# motoko_ice_dragon.net
KiCad netlist of a schematic drawn in EAGLE
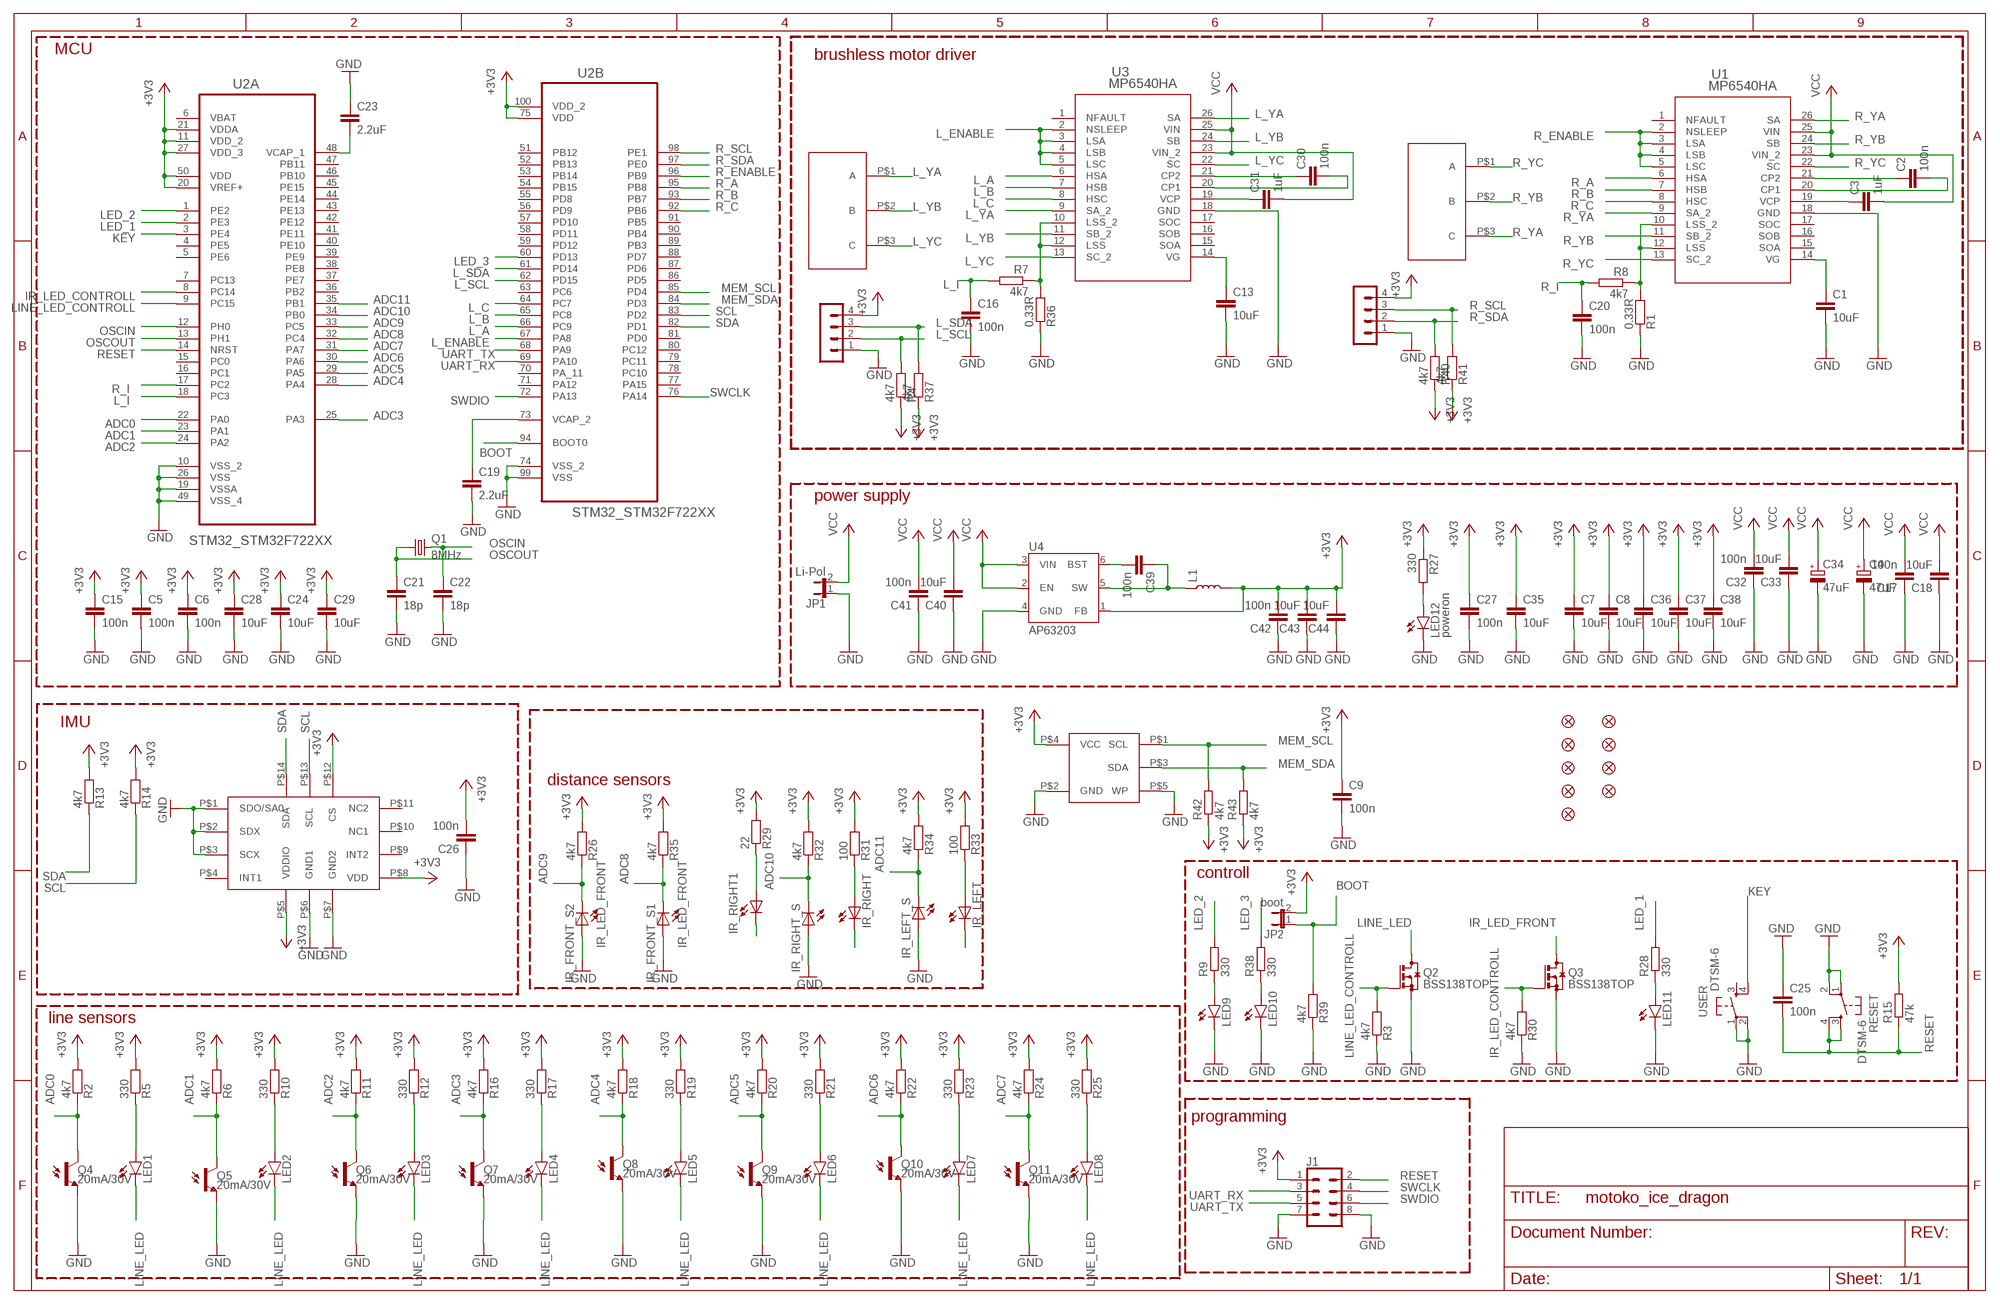
[diagram p0: schematic, sheet 1]

(export (version "E")
  (design (tool "Eeschema 10.0.6"))
  (components
    (comp (ref "C1")
      (value "10uF")
      (footprint "eagle-import:C0805")
      (libsource (lib "eagle-import") (part "C-EUC0805"))
    )
    (comp (ref "C2")
      (value "100n")
      (footprint "eagle-import:C0805")
      (libsource (lib "eagle-import") (part "C-EUC0805"))
    )
    (comp (ref "C3")
      (value "1uF")
      (footprint "eagle-import:C0805")
      (libsource (lib "eagle-import") (part "C-EUC0805"))
    )
    (comp (ref "C4")
      (value "47uF")
      (footprint "eagle-import:140CLH-1010")
      (libsource (lib "eagle-import") (part "CPOL-EU140CLH-1010"))
    )
    (comp (ref "C5")
      (value "100n")
      (footprint "eagle-import:C0805")
      (libsource (lib "eagle-import") (part "C-EUC0805"))
    )
    (comp (ref "C6")
      (value "100n")
      (footprint "eagle-import:C0805")
      (libsource (lib "eagle-import") (part "C-EUC0805"))
    )
    (comp (ref "C7")
      (value "10uF")
      (footprint "eagle-import:C0805")
      (libsource (lib "eagle-import") (part "C-EUC0805"))
    )
    (comp (ref "C8")
      (value "10uF")
      (footprint "eagle-import:C0805")
      (libsource (lib "eagle-import") (part "C-EUC0805"))
    )
    (comp (ref "C9")
      (value "100n")
      (footprint "eagle-import:C0805")
      (libsource (lib "eagle-import") (part "C-EUC0805"))
    )
    (comp (ref "C13")
      (value "10uF")
      (footprint "eagle-import:C0805")
      (libsource (lib "eagle-import") (part "C-EUC0805"))
    )
    (comp (ref "C15")
      (value "100n")
      (footprint "eagle-import:C0805")
      (libsource (lib "eagle-import") (part "C-EUC0805"))
    )
    (comp (ref "C16")
      (value "100n")
      (footprint "eagle-import:C0805")
      (libsource (lib "eagle-import") (part "C-EUC0805"))
    )
    (comp (ref "C17")
      (value "100n")
      (footprint "eagle-import:C0805")
      (libsource (lib "eagle-import") (part "C-EUC0805"))
    )
    (comp (ref "C18")
      (value "10uF")
      (footprint "eagle-import:C0805")
      (libsource (lib "eagle-import") (part "C-EUC0805"))
    )
    (comp (ref "C19")
      (value "2.2uF")
      (footprint "eagle-import:C0805")
      (libsource (lib "eagle-import") (part "C-EUC0805"))
    )
    (comp (ref "C20")
      (value "100n")
      (footprint "eagle-import:C0805")
      (libsource (lib "eagle-import") (part "C-EUC0805"))
    )
    (comp (ref "C21")
      (value "18p")
      (footprint "eagle-import:C0805")
      (libsource (lib "eagle-import") (part "C-EUC0805"))
    )
    (comp (ref "C22")
      (value "18p")
      (footprint "eagle-import:C0805")
      (libsource (lib "eagle-import") (part "C-EUC0805"))
    )
    (comp (ref "C23")
      (value "2.2uF")
      (footprint "eagle-import:C0805")
      (libsource (lib "eagle-import") (part "C-EUC0805"))
    )
    (comp (ref "C24")
      (value "10uF")
      (footprint "eagle-import:C0805")
      (libsource (lib "eagle-import") (part "C-EUC0805"))
    )
    (comp (ref "C25")
      (value "100n")
      (footprint "eagle-import:C0805")
      (libsource (lib "eagle-import") (part "C-EUC0805"))
    )
    (comp (ref "C26")
      (value "100n")
      (footprint "eagle-import:C0805")
      (libsource (lib "eagle-import") (part "C-EUC0805"))
    )
    (comp (ref "C27")
      (value "100n")
      (footprint "eagle-import:C0805")
      (libsource (lib "eagle-import") (part "C-EUC0805"))
    )
    (comp (ref "C28")
      (value "10uF")
      (footprint "eagle-import:C0805")
      (libsource (lib "eagle-import") (part "C-EUC0805"))
    )
    (comp (ref "C29")
      (value "10uF")
      (footprint "eagle-import:C0805")
      (libsource (lib "eagle-import") (part "C-EUC0805"))
    )
    (comp (ref "C30")
      (value "100n")
      (footprint "eagle-import:C0805")
      (libsource (lib "eagle-import") (part "C-EUC0805"))
    )
    (comp (ref "C31")
      (value "1uF")
      (footprint "eagle-import:C0805")
      (libsource (lib "eagle-import") (part "C-EUC0805"))
    )
    (comp (ref "C32")
      (value "100n")
      (footprint "eagle-import:C0805")
      (libsource (lib "eagle-import") (part "C-EUC0805"))
    )
    (comp (ref "C33")
      (value "10uF")
      (footprint "eagle-import:C0805")
      (libsource (lib "eagle-import") (part "C-EUC0805"))
    )
    (comp (ref "C34")
      (value "47uF")
      (footprint "eagle-import:140CLH-1010")
      (libsource (lib "eagle-import") (part "CPOL-EU140CLH-1010"))
    )
    (comp (ref "C35")
      (value "10uF")
      (footprint "eagle-import:C0805")
      (libsource (lib "eagle-import") (part "C-EUC0805"))
    )
    (comp (ref "C36")
      (value "10uF")
      (footprint "eagle-import:C0805")
      (libsource (lib "eagle-import") (part "C-EUC0805"))
    )
    (comp (ref "C37")
      (value "10uF")
      (footprint "eagle-import:C0805")
      (libsource (lib "eagle-import") (part "C-EUC0805"))
    )
    (comp (ref "C38")
      (value "10uF")
      (footprint "eagle-import:C0805")
      (libsource (lib "eagle-import") (part "C-EUC0805"))
    )
    (comp (ref "C39")
      (value "100n")
      (footprint "eagle-import:C0805")
      (libsource (lib "eagle-import") (part "C-EUC0805"))
    )
    (comp (ref "C40")
      (value "10uF")
      (footprint "eagle-import:C0805")
      (libsource (lib "eagle-import") (part "C-EUC0805"))
    )
    (comp (ref "C41")
      (value "100n")
      (footprint "eagle-import:C0805")
      (libsource (lib "eagle-import") (part "C-EUC0805"))
    )
    (comp (ref "C42")
      (value "100n")
      (footprint "eagle-import:C0805")
      (libsource (lib "eagle-import") (part "C-EUC0805"))
    )
    (comp (ref "C43")
      (value "10uF")
      (footprint "eagle-import:C0805")
      (libsource (lib "eagle-import") (part "C-EUC0805"))
    )
    (comp (ref "C44")
      (value "10uF")
      (footprint "eagle-import:C0805")
      (libsource (lib "eagle-import") (part "C-EUC0805"))
    )
    (comp (ref "FD1")
      (value "FIDUCIAL1X2")
      (footprint "eagle-import:FIDUCIAL-1X2")
      (libsource (lib "eagle-import") (part "FIDUCIAL1X2"))
    )
    (comp (ref "FD2")
      (value "FIDUCIAL1X2")
      (footprint "eagle-import:FIDUCIAL-1X2")
      (libsource (lib "eagle-import") (part "FIDUCIAL1X2"))
    )
    (comp (ref "FD3")
      (value "FIDUCIAL1X2")
      (footprint "eagle-import:FIDUCIAL-1X2")
      (libsource (lib "eagle-import") (part "FIDUCIAL1X2"))
    )
    (comp (ref "FD4")
      (value "FIDUCIAL1X2")
      (footprint "eagle-import:FIDUCIAL-1X2")
      (libsource (lib "eagle-import") (part "FIDUCIAL1X2"))
    )
    (comp (ref "FD5")
      (value "FIDUCIAL1X2")
      (footprint "eagle-import:FIDUCIAL-1X2")
      (libsource (lib "eagle-import") (part "FIDUCIAL1X2"))
    )
    (comp (ref "FD6")
      (value "FIDUCIAL1X2")
      (footprint "eagle-import:FIDUCIAL-1X2")
      (libsource (lib "eagle-import") (part "FIDUCIAL1X2"))
    )
    (comp (ref "FD7")
      (value "FIDUCIAL1X2")
      (footprint "eagle-import:FIDUCIAL-1X2")
      (libsource (lib "eagle-import") (part "FIDUCIAL1X2"))
    )
    (comp (ref "FD8")
      (value "FIDUCIAL1X2")
      (footprint "eagle-import:FIDUCIAL-1X2")
      (libsource (lib "eagle-import") (part "FIDUCIAL1X2"))
    )
    (comp (ref "FD9")
      (value "FIDUCIAL1X2")
      (footprint "eagle-import:FIDUCIAL-1X2")
      (libsource (lib "eagle-import") (part "FIDUCIAL1X2"))
    )
    (comp (ref "IR_FRONT_S1")
      (value "LED5MM")
      (footprint "eagle-import:LED5MM")
      (libsource (lib "eagle-import") (part "my_parts_LED5MM"))
    )
    (comp (ref "IR_FRONT_S2")
      (value "LED5MM")
      (footprint "eagle-import:LED5MM")
      (libsource (lib "eagle-import") (part "my_parts_LED5MM"))
    )
    (comp (ref "IR_LEFT")
      (value "LED5MM")
      (footprint "eagle-import:LED5MM")
      (libsource (lib "eagle-import") (part "my_parts_LED5MM"))
    )
    (comp (ref "IR_LEFT_S")
      (value "LED5MM")
      (footprint "eagle-import:LED5MM")
      (libsource (lib "eagle-import") (part "my_parts_LED5MM"))
    )
    (comp (ref "IR_RIGHT")
      (value "LED5MM")
      (footprint "eagle-import:LED5MM")
      (libsource (lib "eagle-import") (part "my_parts_LED5MM"))
    )
    (comp (ref "IR_RIGHT1")
      (value "LED5MM")
      (footprint "eagle-import:LED5MM")
      (libsource (lib "eagle-import") (part "my_parts_LED5MM"))
    )
    (comp (ref "IR_RIGHT_S")
      (value "LED5MM")
      (footprint "eagle-import:LED5MM")
      (libsource (lib "eagle-import") (part "my_parts_LED5MM"))
    )
    (comp (ref "J1")
      (value "CONN_04X2")
      (footprint "eagle-import:2X4")
      (libsource (lib "eagle-import") (part "CONN_04X2"))
    )
    (comp (ref "JP1")
      (value "Li-Pol")
      (footprint "eagle-import:JP1")
      (libsource (lib "eagle-import") (part "JP1E"))
    )
    (comp (ref "JP2")
      (value "boot")
      (footprint "eagle-import:JP1")
      (libsource (lib "eagle-import") (part "JP1E"))
    )
    (comp (ref "L1")
      (value "4.7uH, TYS50204R7N-10")
      (footprint "eagle-import:CR54")
      (libsource (lib "eagle-import") (part "INDUCTOR-CR54-3.3UH"))
    )
    (comp (ref "LED1")
      (value "LEDCHIPLED_1206")
      (footprint "eagle-import:CHIPLED_1206")
      (libsource (lib "eagle-import") (part "LEDCHIPLED_1206"))
    )
    (comp (ref "LED2")
      (value "LEDCHIPLED_1206")
      (footprint "eagle-import:CHIPLED_1206")
      (libsource (lib "eagle-import") (part "LEDCHIPLED_1206"))
    )
    (comp (ref "LED3")
      (value "LEDCHIPLED_1206")
      (footprint "eagle-import:CHIPLED_1206")
      (libsource (lib "eagle-import") (part "LEDCHIPLED_1206"))
    )
    (comp (ref "LED4")
      (value "LEDCHIPLED_1206")
      (footprint "eagle-import:CHIPLED_1206")
      (libsource (lib "eagle-import") (part "LEDCHIPLED_1206"))
    )
    (comp (ref "LED5")
      (value "LEDCHIPLED_1206")
      (footprint "eagle-import:CHIPLED_1206")
      (libsource (lib "eagle-import") (part "LEDCHIPLED_1206"))
    )
    (comp (ref "LED6")
      (value "LEDCHIPLED_1206")
      (footprint "eagle-import:CHIPLED_1206")
      (libsource (lib "eagle-import") (part "LEDCHIPLED_1206"))
    )
    (comp (ref "LED7")
      (value "LEDCHIPLED_1206")
      (footprint "eagle-import:CHIPLED_1206")
      (libsource (lib "eagle-import") (part "LEDCHIPLED_1206"))
    )
    (comp (ref "LED8")
      (value "LEDCHIPLED_1206")
      (footprint "eagle-import:CHIPLED_1206")
      (libsource (lib "eagle-import") (part "LEDCHIPLED_1206"))
    )
    (comp (ref "LED9")
      (value "LEDCHIPLED_1206")
      (footprint "eagle-import:CHIPLED_1206")
      (libsource (lib "eagle-import") (part "LEDCHIPLED_1206"))
    )
    (comp (ref "LED10")
      (value "LEDCHIPLED_1206")
      (footprint "eagle-import:CHIPLED_1206")
      (libsource (lib "eagle-import") (part "LEDCHIPLED_1206"))
    )
    (comp (ref "LED11")
      (value "LEDCHIPLED_1206")
      (footprint "eagle-import:CHIPLED_1206")
      (libsource (lib "eagle-import") (part "LEDCHIPLED_1206"))
    )
    (comp (ref "LED12")
      (value "poweron")
      (footprint "eagle-import:CHIPLED_1206")
      (libsource (lib "eagle-import") (part "LEDCHIPLED_1206"))
    )
    (comp (ref "L_ENCODER")
      (value "MA04-1")
      (footprint "eagle-import:MA04-1")
      (libsource (lib "eagle-import") (part "MA04-1"))
    )
    (comp (ref "L_ENCODER1")
      (value "MA04-1")
      (footprint "eagle-import:MA04-1")
      (libsource (lib "eagle-import") (part "MA04-1"))
    )
    (comp (ref "Q1")
      (value "8MHz")
      (footprint "eagle-import:CTS406")
      (libsource (lib "eagle-import") (part "CRYSTALCTS406"))
    )
    (comp (ref "Q2")
      (value "BSS138TOP")
      (footprint "eagle-import:SOT23")
      (libsource (lib "eagle-import") (part "BSS138TOP"))
    )
    (comp (ref "Q3")
      (value "BSS138TOP")
      (footprint "eagle-import:SOT23")
      (libsource (lib "eagle-import") (part "BSS138TOP"))
    )
    (comp (ref "Q4")
      (value "20mA/30V")
      (footprint "eagle-import:PT17-21C-L41-TR8")
      (libsource (lib "eagle-import") (part "PHOTOTRANSISTORPT17-21C-L41-TR8"))
    )
    (comp (ref "Q5")
      (value "20mA/30V")
      (footprint "eagle-import:PT17-21C-L41-TR8")
      (libsource (lib "eagle-import") (part "PHOTOTRANSISTORPT17-21C-L41-TR8"))
    )
    (comp (ref "Q6")
      (value "20mA/30V")
      (footprint "eagle-import:PT17-21C-L41-TR8")
      (libsource (lib "eagle-import") (part "PHOTOTRANSISTORPT17-21C-L41-TR8"))
    )
    (comp (ref "Q7")
      (value "20mA/30V")
      (footprint "eagle-import:PT17-21C-L41-TR8")
      (libsource (lib "eagle-import") (part "PHOTOTRANSISTORPT17-21C-L41-TR8"))
    )
    (comp (ref "Q8")
      (value "20mA/30V")
      (footprint "eagle-import:PT17-21C-L41-TR8")
      (libsource (lib "eagle-import") (part "PHOTOTRANSISTORPT17-21C-L41-TR8"))
    )
    (comp (ref "Q9")
      (value "20mA/30V")
      (footprint "eagle-import:PT17-21C-L41-TR8")
      (libsource (lib "eagle-import") (part "PHOTOTRANSISTORPT17-21C-L41-TR8"))
    )
    (comp (ref "Q10")
      (value "20mA/30V")
      (footprint "eagle-import:PT17-21C-L41-TR8")
      (libsource (lib "eagle-import") (part "PHOTOTRANSISTORPT17-21C-L41-TR8"))
    )
    (comp (ref "Q11")
      (value "20mA/30V")
      (footprint "eagle-import:PT17-21C-L41-TR8")
      (libsource (lib "eagle-import") (part "PHOTOTRANSISTORPT17-21C-L41-TR8"))
    )
    (comp (ref "R1")
      (value "0.33R")
      (footprint "eagle-import:M1206")
      (libsource (lib "eagle-import") (part "R-EU_M1206"))
    )
    (comp (ref "R2")
      (value "4k7")
      (footprint "eagle-import:M0805")
      (libsource (lib "eagle-import") (part "resistor_348_R-EU_M0805"))
    )
    (comp (ref "R3")
      (value "4k7")
      (footprint "eagle-import:M0805")
      (libsource (lib "eagle-import") (part "resistor_348_R-EU_M0805"))
    )
    (comp (ref "R4")
      (value "4k7")
      (footprint "eagle-import:M0805")
      (libsource (lib "eagle-import") (part "resistor_348_R-EU_M0805"))
    )
    (comp (ref "R5")
      (value "330")
      (footprint "eagle-import:M0805")
      (libsource (lib "eagle-import") (part "resistor_348_R-EU_M0805"))
    )
    (comp (ref "R6")
      (value "4k7")
      (footprint "eagle-import:M0805")
      (libsource (lib "eagle-import") (part "resistor_348_R-EU_M0805"))
    )
    (comp (ref "R7")
      (value "4k7")
      (footprint "eagle-import:M0805")
      (libsource (lib "eagle-import") (part "resistor_348_R-EU_M0805"))
    )
    (comp (ref "R8")
      (value "4k7")
      (footprint "eagle-import:M0805")
      (libsource (lib "eagle-import") (part "resistor_348_R-EU_M0805"))
    )
    (comp (ref "R9")
      (value "330")
      (footprint "eagle-import:M0805")
      (libsource (lib "eagle-import") (part "resistor_348_R-EU_M0805"))
    )
    (comp (ref "R10")
      (value "330")
      (footprint "eagle-import:M0805")
      (libsource (lib "eagle-import") (part "resistor_348_R-EU_M0805"))
    )
    (comp (ref "R11")
      (value "4k7")
      (footprint "eagle-import:M0805")
      (libsource (lib "eagle-import") (part "resistor_348_R-EU_M0805"))
    )
    (comp (ref "R12")
      (value "330")
      (footprint "eagle-import:M0805")
      (libsource (lib "eagle-import") (part "resistor_348_R-EU_M0805"))
    )
    (comp (ref "R13")
      (value "4k7")
      (footprint "eagle-import:M0805")
      (libsource (lib "eagle-import") (part "resistor_348_R-EU_M0805"))
    )
    (comp (ref "R14")
      (value "4k7")
      (footprint "eagle-import:M0805")
      (libsource (lib "eagle-import") (part "resistor_348_R-EU_M0805"))
    )
    (comp (ref "R15")
      (value "47k")
      (footprint "eagle-import:M0805")
      (libsource (lib "eagle-import") (part "resistor_348_R-EU_M0805"))
    )
    (comp (ref "R16")
      (value "4k7")
      (footprint "eagle-import:M0805")
      (libsource (lib "eagle-import") (part "resistor_348_R-EU_M0805"))
    )
    (comp (ref "R17")
      (value "330")
      (footprint "eagle-import:M0805")
      (libsource (lib "eagle-import") (part "resistor_348_R-EU_M0805"))
    )
    (comp (ref "R18")
      (value "4k7")
      (footprint "eagle-import:M0805")
      (libsource (lib "eagle-import") (part "resistor_348_R-EU_M0805"))
    )
    (comp (ref "R19")
      (value "330")
      (footprint "eagle-import:M0805")
      (libsource (lib "eagle-import") (part "resistor_348_R-EU_M0805"))
    )
    (comp (ref "R20")
      (value "4k7")
      (footprint "eagle-import:M0805")
      (libsource (lib "eagle-import") (part "resistor_348_R-EU_M0805"))
    )
    (comp (ref "R21")
      (value "330")
      (footprint "eagle-import:M0805")
      (libsource (lib "eagle-import") (part "resistor_348_R-EU_M0805"))
    )
    (comp (ref "R22")
      (value "4k7")
      (footprint "eagle-import:M0805")
      (libsource (lib "eagle-import") (part "resistor_348_R-EU_M0805"))
    )
    (comp (ref "R23")
      (value "330")
      (footprint "eagle-import:M0805")
      (libsource (lib "eagle-import") (part "resistor_348_R-EU_M0805"))
    )
    (comp (ref "R24")
      (value "4k7")
      (footprint "eagle-import:M0805")
      (libsource (lib "eagle-import") (part "resistor_348_R-EU_M0805"))
    )
    (comp (ref "R25")
      (value "330")
      (footprint "eagle-import:M0805")
      (libsource (lib "eagle-import") (part "resistor_348_R-EU_M0805"))
    )
    (comp (ref "R26")
      (value "4k7")
      (footprint "eagle-import:M0805")
      (libsource (lib "eagle-import") (part "resistor_348_R-EU_M0805"))
    )
    (comp (ref "R27")
      (value "330")
      (footprint "eagle-import:M0805")
      (libsource (lib "eagle-import") (part "resistor_348_R-EU_M0805"))
    )
    (comp (ref "R28")
      (value "330")
      (footprint "eagle-import:M0805")
      (libsource (lib "eagle-import") (part "resistor_348_R-EU_M0805"))
    )
    (comp (ref "R29")
      (value "22")
      (footprint "eagle-import:M0805")
      (libsource (lib "eagle-import") (part "resistor_348_R-EU_M0805"))
    )
    (comp (ref "R30")
      (value "4k7")
      (footprint "eagle-import:M0805")
      (libsource (lib "eagle-import") (part "resistor_348_R-EU_M0805"))
    )
    (comp (ref "R31")
      (value "100")
      (footprint "eagle-import:M0805")
      (libsource (lib "eagle-import") (part "resistor_348_R-EU_M0805"))
    )
    (comp (ref "R32")
      (value "4k7")
      (footprint "eagle-import:M0805")
      (libsource (lib "eagle-import") (part "resistor_348_R-EU_M0805"))
    )
    (comp (ref "R33")
      (value "100")
      (footprint "eagle-import:M0805")
      (libsource (lib "eagle-import") (part "resistor_348_R-EU_M0805"))
    )
    (comp (ref "R34")
      (value "4k7")
      (footprint "eagle-import:M0805")
      (libsource (lib "eagle-import") (part "resistor_348_R-EU_M0805"))
    )
    (comp (ref "R35")
      (value "4k7")
      (footprint "eagle-import:M0805")
      (libsource (lib "eagle-import") (part "resistor_348_R-EU_M0805"))
    )
    (comp (ref "R36")
      (value "0.33R")
      (footprint "eagle-import:M1206")
      (libsource (lib "eagle-import") (part "R-EU_M1206"))
    )
    (comp (ref "R37")
      (value "4k7")
      (footprint "eagle-import:M0805")
      (libsource (lib "eagle-import") (part "resistor_348_R-EU_M0805"))
    )
    (comp (ref "R38")
      (value "330")
      (footprint "eagle-import:M0805")
      (libsource (lib "eagle-import") (part "resistor_348_R-EU_M0805"))
    )
    (comp (ref "R39")
      (value "4k7")
      (footprint "eagle-import:M0805")
      (libsource (lib "eagle-import") (part "resistor_348_R-EU_M0805"))
    )
    (comp (ref "R40")
      (value "4k7")
      (footprint "eagle-import:M0805")
      (libsource (lib "eagle-import") (part "resistor_348_R-EU_M0805"))
    )
    (comp (ref "R41")
      (value "4k7")
      (footprint "eagle-import:M0805")
      (libsource (lib "eagle-import") (part "resistor_348_R-EU_M0805"))
    )
    (comp (ref "R42")
      (value "4k7")
      (footprint "eagle-import:M0805")
      (libsource (lib "eagle-import") (part "R-EU_M0805"))
    )
    (comp (ref "R43")
      (value "4k7")
      (footprint "eagle-import:M0805")
      (libsource (lib "eagle-import") (part "R-EU_M0805"))
    )
    (comp (ref "RESET")
      (value "DTSM-6")
      (footprint "eagle-import:DTSM-6")
      (libsource (lib "eagle-import") (part "DTSM-6"))
    )
    (comp (ref "U$1")
      (value "BRUSHLESS_GIMBAL_MOTOR_WHEEL")
      (footprint "eagle-import:BRUSHLESS_GIMBAL_MOTOR_WHEEL")
      (libsource (lib "eagle-import") (part "BRUSHLESS_GIMBAL_MOTOR_WHEEL"))
    )
    (comp (ref "U$2")
      (value "BRUSHLESS_GIMBAL_MOTOR_WHEEL")
      (footprint "eagle-import:BRUSHLESS_GIMBAL_MOTOR_WHEEL")
      (libsource (lib "eagle-import") (part "BRUSHLESS_GIMBAL_MOTOR_WHEEL"))
    )
    (comp (ref "U$3")
      (value "LSM6DSM")
      (footprint "eagle-import:LGA14L")
      (libsource (lib "eagle-import") (part "LSM6DSM"))
    )
    (comp (ref "U$4")
      (value "24LC24_SOT23")
      (footprint "eagle-import:SOT23")
      (libsource (lib "eagle-import") (part "24LC24_SOT23"))
    )
    (comp (ref "U1")
      (value "MP6540HA")
      (footprint "eagle-import:QFN-5X5_MP6540HA_MNP")
      (fields (field (name "COPYRIGHT") "Copyright (C) 2018 Accelerated Designs. All rights reserved"))
      (libsource (lib "eagle-import") (part "MP6540HA"))
    )
    (comp (ref "U2")
      (value "STM32_STM32F722XX")
      (footprint "eagle-import:STM32_QFP50P1600X1600X160-100N")
      (fields (field (name "MPN") "STM32F407VET6"))
      (libsource (lib "eagle-import") (part "STM32_STM32F722XX"))
    )
    (comp (ref "U3")
      (value "MP6540HA")
      (footprint "eagle-import:QFN-5X5_MP6540HA_MNP")
      (fields (field (name "COPYRIGHT") "Copyright (C) 2018 Accelerated Designs. All rights reserved"))
      (libsource (lib "eagle-import") (part "MP6540HA"))
    )
    (comp (ref "U4")
      (value "AP63203")
      (footprint "eagle-import:SOT23-6")
      (libsource (lib "eagle-import") (part "AP63203"))
    )
    (comp (ref "USER")
      (value "DTSM-6")
      (footprint "eagle-import:DTSM-6")
      (libsource (lib "eagle-import") (part "DTSM-6"))
    )
  )
  (nets
    (net (code "1") (name "+3V3") (class "Default")
      (node (ref "C15") (pin "1") (pinfunction "1_1") (pintype "passive"))
      (node (ref "C24") (pin "1") (pinfunction "1_1") (pintype "passive"))
      (node (ref "C26") (pin "2") (pinfunction "2_2") (pintype "passive"))
      (node (ref "C27") (pin "1") (pinfunction "1_1") (pintype "passive"))
      (node (ref "C28") (pin "1") (pinfunction "1_1") (pintype "passive"))
      (node (ref "C29") (pin "1") (pinfunction "1_1") (pintype "passive"))
      (node (ref "C35") (pin "1") (pinfunction "1_1") (pintype "passive"))
      (node (ref "C36") (pin "1") (pinfunction "1_1") (pintype "passive"))
      (node (ref "C37") (pin "1") (pinfunction "1_1") (pintype "passive"))
      (node (ref "C38") (pin "1") (pinfunction "1_1") (pintype "passive"))
      (node (ref "C42") (pin "2") (pinfunction "2_2") (pintype "passive"))
      (node (ref "C43") (pin "2") (pinfunction "2_2") (pintype "passive"))
      (node (ref "C44") (pin "2") (pinfunction "2_2") (pintype "passive"))
      (node (ref "C5") (pin "1") (pinfunction "1_1") (pintype "passive"))
      (node (ref "C6") (pin "1") (pinfunction "1_1") (pintype "passive"))
      (node (ref "C7") (pin "1") (pinfunction "1_1") (pintype "passive"))
      (node (ref "C8") (pin "1") (pinfunction "1_1") (pintype "passive"))
      (node (ref "C9") (pin "1") (pinfunction "1_1") (pintype "passive"))
      (node (ref "J1") (pin "1") (pinfunction "1_1") (pintype "passive"))
      (node (ref "JP2") (pin "2") (pinfunction "2_2") (pintype "passive"))
      (node (ref "L1") (pin "P$2") (pinfunction "2_P$2") (pintype "passive"))
      (node (ref "L_ENCODER") (pin "4") (pinfunction "4_4") (pintype "passive"))
      (node (ref "L_ENCODER1") (pin "4") (pinfunction "4_4") (pintype "passive"))
      (node (ref "R10") (pin "2") (pinfunction "2_2") (pintype "passive"))
      (node (ref "R11") (pin "2") (pinfunction "2_2") (pintype "passive"))
      (node (ref "R12") (pin "2") (pinfunction "2_2") (pintype "passive"))
      (node (ref "R13") (pin "2") (pinfunction "2_2") (pintype "passive"))
      (node (ref "R14") (pin "2") (pinfunction "2_2") (pintype "passive"))
      (node (ref "R15") (pin "2") (pinfunction "2_2") (pintype "passive"))
      (node (ref "R16") (pin "2") (pinfunction "2_2") (pintype "passive"))
      (node (ref "R17") (pin "2") (pinfunction "2_2") (pintype "passive"))
      (node (ref "R18") (pin "2") (pinfunction "2_2") (pintype "passive"))
      (node (ref "R19") (pin "2") (pinfunction "2_2") (pintype "passive"))
      (node (ref "R2") (pin "2") (pinfunction "2_2") (pintype "passive"))
      (node (ref "R20") (pin "2") (pinfunction "2_2") (pintype "passive"))
      (node (ref "R21") (pin "2") (pinfunction "2_2") (pintype "passive"))
      (node (ref "R22") (pin "2") (pinfunction "2_2") (pintype "passive"))
      (node (ref "R23") (pin "2") (pinfunction "2_2") (pintype "passive"))
      (node (ref "R24") (pin "2") (pinfunction "2_2") (pintype "passive"))
      (node (ref "R25") (pin "2") (pinfunction "2_2") (pintype "passive"))
      (node (ref "R26") (pin "2") (pinfunction "2_2") (pintype "passive"))
      (node (ref "R27") (pin "1") (pinfunction "1_1") (pintype "passive"))
      (node (ref "R29") (pin "2") (pinfunction "2_2") (pintype "passive"))
      (node (ref "R31") (pin "2") (pinfunction "2_2") (pintype "passive"))
      (node (ref "R32") (pin "2") (pinfunction "2_2") (pintype "passive"))
      (node (ref "R33") (pin "2") (pinfunction "2_2") (pintype "passive"))
      (node (ref "R34") (pin "2") (pinfunction "2_2") (pintype "passive"))
      (node (ref "R35") (pin "2") (pinfunction "2_2") (pintype "passive"))
      (node (ref "R37") (pin "1") (pinfunction "1_1") (pintype "passive"))
      (node (ref "R4") (pin "1") (pinfunction "1_1") (pintype "passive"))
      (node (ref "R40") (pin "1") (pinfunction "1_1") (pintype "passive"))
      (node (ref "R41") (pin "1") (pinfunction "1_1") (pintype "passive"))
      (node (ref "R42") (pin "1") (pinfunction "1_1") (pintype "passive"))
      (node (ref "R43") (pin "1") (pinfunction "1_1") (pintype "passive"))
      (node (ref "R5") (pin "2") (pinfunction "2_2") (pintype "passive"))
      (node (ref "R6") (pin "2") (pinfunction "2_2") (pintype "passive"))
      (node (ref "U$3") (pin "P$12") (pinfunction "CS_P$12") (pintype "bidirectional"))
      (node (ref "U$3") (pin "P$5") (pinfunction "VDDIO_P$5") (pintype "bidirectional"))
      (node (ref "U$3") (pin "P$8") (pinfunction "VDD_P$8") (pintype "bidirectional"))
      (node (ref "U$4") (pin "P$4") (pinfunction "VCC_P$4") (pintype "bidirectional"))
      (node (ref "U2") (pin "100") (pinfunction "VDD_2_100") (pintype "power_in"))
      (node (ref "U2") (pin "11") (pinfunction "VDD_2_11") (pintype "power_in"))
      (node (ref "U2") (pin "20") (pinfunction "VREF+_20") (pintype "power_in"))
      (node (ref "U2") (pin "21") (pinfunction "VDDA_21") (pintype "power_in"))
      (node (ref "U2") (pin "27") (pinfunction "VDD_3_27") (pintype "power_in"))
      (node (ref "U2") (pin "50") (pinfunction "VDD_50") (pintype "power_in"))
      (node (ref "U2") (pin "75") (pinfunction "VDD_75") (pintype "power_in"))
      (node (ref "U4") (pin "1") (pinfunction "FB_1") (pintype "bidirectional"))
    )
    (net (code "2") (name "/ADC0") (class "Default")
      (node (ref "Q4") (pin "C") (pinfunction "C_C") (pintype "passive"))
      (node (ref "R2") (pin "1") (pinfunction "1_1") (pintype "passive"))
      (node (ref "U2") (pin "22") (pinfunction "PA0_22") (pintype "bidirectional"))
    )
    (net (code "3") (name "/ADC1") (class "Default")
      (node (ref "Q5") (pin "C") (pinfunction "C_C") (pintype "passive"))
      (node (ref "R6") (pin "1") (pinfunction "1_1") (pintype "passive"))
      (node (ref "U2") (pin "23") (pinfunction "PA1_23") (pintype "bidirectional"))
    )
    (net (code "4") (name "/ADC2") (class "Default")
      (node (ref "Q6") (pin "C") (pinfunction "C_C") (pintype "passive"))
      (node (ref "R11") (pin "1") (pinfunction "1_1") (pintype "passive"))
      (node (ref "U2") (pin "24") (pinfunction "PA2_24") (pintype "bidirectional"))
    )
    (net (code "5") (name "/ADC3") (class "Default")
      (node (ref "Q7") (pin "C") (pinfunction "C_C") (pintype "passive"))
      (node (ref "R16") (pin "1") (pinfunction "1_1") (pintype "passive"))
      (node (ref "U2") (pin "25") (pinfunction "PA3_25") (pintype "bidirectional"))
    )
    (net (code "6") (name "/ADC4") (class "Default")
      (node (ref "Q8") (pin "C") (pinfunction "C_C") (pintype "passive"))
      (node (ref "R18") (pin "1") (pinfunction "1_1") (pintype "passive"))
      (node (ref "U2") (pin "28") (pinfunction "PA4_28") (pintype "bidirectional"))
    )
    (net (code "7") (name "/ADC5") (class "Default")
      (node (ref "Q9") (pin "C") (pinfunction "C_C") (pintype "passive"))
      (node (ref "R20") (pin "1") (pinfunction "1_1") (pintype "passive"))
      (node (ref "U2") (pin "29") (pinfunction "PA5_29") (pintype "bidirectional"))
    )
    (net (code "8") (name "/ADC6") (class "Default")
      (node (ref "Q10") (pin "C") (pinfunction "C_C") (pintype "passive"))
      (node (ref "R22") (pin "1") (pinfunction "1_1") (pintype "passive"))
      (node (ref "U2") (pin "30") (pinfunction "PA6_30") (pintype "bidirectional"))
    )
    (net (code "9") (name "/ADC7") (class "Default")
      (node (ref "Q11") (pin "C") (pinfunction "C_C") (pintype "passive"))
      (node (ref "R24") (pin "1") (pinfunction "1_1") (pintype "passive"))
      (node (ref "U2") (pin "31") (pinfunction "PA7_31") (pintype "bidirectional"))
    )
    (net (code "10") (name "/ADC8") (class "Default")
      (node (ref "IR_FRONT_S1") (pin "K") (pinfunction "C_K") (pintype "passive"))
      (node (ref "R35") (pin "1") (pinfunction "1_1") (pintype "passive"))
      (node (ref "U2") (pin "32") (pinfunction "PC4_32") (pintype "bidirectional"))
    )
    (net (code "11") (name "/ADC9") (class "Default")
      (node (ref "IR_FRONT_S2") (pin "K") (pinfunction "C_K") (pintype "passive"))
      (node (ref "R26") (pin "1") (pinfunction "1_1") (pintype "passive"))
      (node (ref "U2") (pin "33") (pinfunction "PC5_33") (pintype "bidirectional"))
    )
    (net (code "12") (name "/ADC10") (class "Default")
      (node (ref "IR_RIGHT_S") (pin "K") (pinfunction "C_K") (pintype "passive"))
      (node (ref "R32") (pin "1") (pinfunction "1_1") (pintype "passive"))
      (node (ref "U2") (pin "34") (pinfunction "PB0_34") (pintype "bidirectional"))
    )
    (net (code "13") (name "/ADC11") (class "Default")
      (node (ref "IR_LEFT_S") (pin "K") (pinfunction "C_K") (pintype "passive"))
      (node (ref "R34") (pin "1") (pinfunction "1_1") (pintype "passive"))
      (node (ref "U2") (pin "35") (pinfunction "PB1_35") (pintype "bidirectional"))
    )
    (net (code "14") (name "/BOOT") (class "Default")
      (node (ref "JP2") (pin "1") (pinfunction "1_1") (pintype "passive"))
      (node (ref "R39") (pin "2") (pinfunction "2_2") (pintype "passive"))
      (node (ref "U2") (pin "94") (pinfunction "BOOT0_94") (pintype "input"))
    )
    (net (code "15") (name "/IR_LED_CONTROLL") (class "Default")
      (node (ref "Q3") (pin "1") (pinfunction "G_1") (pintype "passive"))
      (node (ref "R30") (pin "2") (pinfunction "2_2") (pintype "passive"))
      (node (ref "U2") (pin "8") (pinfunction "PC14_8") (pintype "bidirectional"))
    )
    (net (code "16") (name "/IR_LED_FRONT") (class "Default")
      (node (ref "IR_LEFT") (pin "K") (pinfunction "C_K") (pintype "passive"))
      (node (ref "IR_RIGHT") (pin "K") (pinfunction "C_K") (pintype "passive"))
      (node (ref "IR_RIGHT1") (pin "K") (pinfunction "C_K") (pintype "passive"))
      (node (ref "Q3") (pin "3") (pinfunction "D_3") (pintype "passive"))
    )
    (net (code "17") (name "/KEY") (class "Default")
      (node (ref "U2") (pin "3") (pinfunction "PE4_3") (pintype "bidirectional"))
      (node (ref "USER") (pin "4") (pinfunction "4_4") (pintype "passive"))
    )
    (net (code "18") (name "/LED_1") (class "Default")
      (node (ref "R28") (pin "2") (pinfunction "2_2") (pintype "passive"))
      (node (ref "U2") (pin "2") (pinfunction "PE3_2") (pintype "bidirectional"))
    )
    (net (code "19") (name "/LED_2") (class "Default")
      (node (ref "R9") (pin "2") (pinfunction "2_2") (pintype "passive"))
      (node (ref "U2") (pin "1") (pinfunction "PE2_1") (pintype "bidirectional"))
    )
    (net (code "20") (name "/LED_3") (class "Default")
      (node (ref "R38") (pin "2") (pinfunction "2_2") (pintype "passive"))
      (node (ref "U2") (pin "60") (pinfunction "PD13_60") (pintype "bidirectional"))
    )
    (net (code "21") (name "/LINE_LED") (class "Default")
      (node (ref "LED1") (pin "C") (pinfunction "C_C") (pintype "passive"))
      (node (ref "LED2") (pin "C") (pinfunction "C_C") (pintype "passive"))
      (node (ref "LED3") (pin "C") (pinfunction "C_C") (pintype "passive"))
      (node (ref "LED4") (pin "C") (pinfunction "C_C") (pintype "passive"))
      (node (ref "LED5") (pin "C") (pinfunction "C_C") (pintype "passive"))
      (node (ref "LED6") (pin "C") (pinfunction "C_C") (pintype "passive"))
      (node (ref "LED7") (pin "C") (pinfunction "C_C") (pintype "passive"))
      (node (ref "LED8") (pin "C") (pinfunction "C_C") (pintype "passive"))
      (node (ref "Q2") (pin "3") (pinfunction "D_3") (pintype "passive"))
    )
    (net (code "22") (name "/LINE_LED_CONTROLL") (class "Default")
      (node (ref "Q2") (pin "1") (pinfunction "G_1") (pintype "passive"))
      (node (ref "R3") (pin "2") (pinfunction "2_2") (pintype "passive"))
      (node (ref "U2") (pin "9") (pinfunction "PC15_9") (pintype "bidirectional"))
    )
    (net (code "23") (name "/L_A") (class "Default")
      (node (ref "U2") (pin "66") (pinfunction "PC9_66") (pintype "bidirectional"))
      (node (ref "U3") (pin "6") (pinfunction "HSA_6") (pintype "passive"))
    )
    (net (code "24") (name "/L_B") (class "Default")
      (node (ref "U2") (pin "65") (pinfunction "PC8_65") (pintype "bidirectional"))
      (node (ref "U3") (pin "7") (pinfunction "HSB_7") (pintype "passive"))
    )
    (net (code "25") (name "/L_C") (class "Default")
      (node (ref "U2") (pin "64") (pinfunction "PC7_64") (pintype "bidirectional"))
      (node (ref "U3") (pin "8") (pinfunction "HSC_8") (pintype "passive"))
    )
    (net (code "26") (name "/L_ENABLE") (class "Default")
      (node (ref "U2") (pin "67") (pinfunction "PA8_67") (pintype "bidirectional"))
      (node (ref "U3") (pin "2") (pinfunction "NSLEEP_2") (pintype "input"))
      (node (ref "U3") (pin "3") (pinfunction "LSA_3") (pintype "passive"))
      (node (ref "U3") (pin "4") (pinfunction "LSB_4") (pintype "passive"))
      (node (ref "U3") (pin "5") (pinfunction "LSC_5") (pintype "passive"))
    )
    (net (code "27") (name "/L_I") (class "Default")
      (node (ref "C16") (pin "1") (pinfunction "1_1") (pintype "passive"))
      (node (ref "R7") (pin "2") (pinfunction "2_2") (pintype "passive"))
      (node (ref "U2") (pin "18") (pinfunction "PC3_18") (pintype "bidirectional"))
    )
    (net (code "28") (name "/L_SCL") (class "Default")
      (node (ref "L_ENCODER") (pin "2") (pinfunction "2_2") (pintype "passive"))
      (node (ref "R4") (pin "2") (pinfunction "2_2") (pintype "passive"))
      (node (ref "U2") (pin "62") (pinfunction "PD15_62") (pintype "bidirectional"))
    )
    (net (code "29") (name "/L_SDA") (class "Default")
      (node (ref "L_ENCODER") (pin "3") (pinfunction "3_3") (pintype "passive"))
      (node (ref "R37") (pin "2") (pinfunction "2_2") (pintype "passive"))
      (node (ref "U2") (pin "61") (pinfunction "PD14_61") (pintype "bidirectional"))
    )
    (net (code "30") (name "/L_YA") (class "Default")
      (node (ref "U$1") (pin "P$1") (pinfunction "A_P$1") (pintype "input"))
      (node (ref "U3") (pin "26") (pinfunction "SA_26") (pintype "output"))
      (node (ref "U3") (pin "9") (pinfunction "SA_2_9") (pintype "output"))
    )
    (net (code "31") (name "/L_YB") (class "Default")
      (node (ref "U$1") (pin "P$2") (pinfunction "B_P$2") (pintype "input"))
      (node (ref "U3") (pin "11") (pinfunction "SB_2_11") (pintype "output"))
      (node (ref "U3") (pin "24") (pinfunction "SB_24") (pintype "output"))
    )
    (net (code "32") (name "/L_YC") (class "Default")
      (node (ref "U$1") (pin "P$3") (pinfunction "C_P$3") (pintype "input"))
      (node (ref "U3") (pin "13") (pinfunction "SC_2_13") (pintype "output"))
      (node (ref "U3") (pin "22") (pinfunction "SC_22") (pintype "output"))
    )
    (net (code "33") (name "/MEM_SCL") (class "Default")
      (node (ref "R42") (pin "2") (pinfunction "2_2") (pintype "passive"))
      (node (ref "U$4") (pin "P$1") (pinfunction "SCL_P$1") (pintype "bidirectional"))
      (node (ref "U2") (pin "85") (pinfunction "PD4_85") (pintype "bidirectional"))
    )
    (net (code "34") (name "/MEM_SDA") (class "Default")
      (node (ref "R43") (pin "2") (pinfunction "2_2") (pintype "passive"))
      (node (ref "U$4") (pin "P$3") (pinfunction "SDA_P$3") (pintype "bidirectional"))
      (node (ref "U2") (pin "84") (pinfunction "PD3_84") (pintype "bidirectional"))
    )
    (net (code "35") (name "/OSCIN") (class "Default")
      (node (ref "C22") (pin "1") (pinfunction "1_1") (pintype "passive"))
      (node (ref "Q1") (pin "3") (pinfunction "2_3") (pintype "passive"))
      (node (ref "U2") (pin "12") (pinfunction "PH0_12") (pintype "bidirectional"))
    )
    (net (code "36") (name "/OSCOUT") (class "Default")
      (node (ref "C21") (pin "1") (pinfunction "1_1") (pintype "passive"))
      (node (ref "Q1") (pin "1") (pinfunction "1_1") (pintype "passive"))
      (node (ref "U2") (pin "13") (pinfunction "PH1_13") (pintype "bidirectional"))
    )
    (net (code "37") (name "/RESET") (class "Default")
      (node (ref "C25") (pin "2") (pinfunction "2_2") (pintype "passive"))
      (node (ref "J1") (pin "2") (pinfunction "2_2") (pintype "passive"))
      (node (ref "R15") (pin "1") (pinfunction "1_1") (pintype "passive"))
      (node (ref "RESET") (pin "3") (pinfunction "3_3") (pintype "passive"))
      (node (ref "RESET") (pin "4") (pinfunction "4_4") (pintype "passive"))
      (node (ref "U2") (pin "14") (pinfunction "NRST_14") (pintype "bidirectional"))
    )
    (net (code "38") (name "/R_A") (class "Default")
      (node (ref "U1") (pin "6") (pinfunction "HSA_6") (pintype "passive"))
      (node (ref "U2") (pin "95") (pinfunction "PB8_95") (pintype "bidirectional"))
    )
    (net (code "39") (name "/R_B") (class "Default")
      (node (ref "U1") (pin "7") (pinfunction "HSB_7") (pintype "passive"))
      (node (ref "U2") (pin "93") (pinfunction "PB7_93") (pintype "bidirectional"))
    )
    (net (code "40") (name "/R_C") (class "Default")
      (node (ref "U1") (pin "8") (pinfunction "HSC_8") (pintype "passive"))
      (node (ref "U2") (pin "92") (pinfunction "PB6_92") (pintype "bidirectional"))
    )
    (net (code "41") (name "/R_ENABLE") (class "Default")
      (node (ref "U1") (pin "2") (pinfunction "NSLEEP_2") (pintype "input"))
      (node (ref "U1") (pin "3") (pinfunction "LSA_3") (pintype "passive"))
      (node (ref "U1") (pin "4") (pinfunction "LSB_4") (pintype "passive"))
      (node (ref "U1") (pin "5") (pinfunction "LSC_5") (pintype "passive"))
      (node (ref "U2") (pin "96") (pinfunction "PB9_96") (pintype "bidirectional"))
    )
    (net (code "42") (name "/R_I") (class "Default")
      (node (ref "C20") (pin "1") (pinfunction "1_1") (pintype "passive"))
      (node (ref "R8") (pin "2") (pinfunction "2_2") (pintype "passive"))
      (node (ref "U2") (pin "17") (pinfunction "PC2_17") (pintype "bidirectional"))
    )
    (net (code "43") (name "/R_SCL") (class "Default")
      (node (ref "L_ENCODER1") (pin "3") (pinfunction "3_3") (pintype "passive"))
      (node (ref "R41") (pin "2") (pinfunction "2_2") (pintype "passive"))
      (node (ref "U2") (pin "98") (pinfunction "PE1_98") (pintype "bidirectional"))
    )
    (net (code "44") (name "/R_SDA") (class "Default")
      (node (ref "L_ENCODER1") (pin "2") (pinfunction "2_2") (pintype "passive"))
      (node (ref "R40") (pin "2") (pinfunction "2_2") (pintype "passive"))
      (node (ref "U2") (pin "97") (pinfunction "PE0_97") (pintype "bidirectional"))
    )
    (net (code "45") (name "/R_YA") (class "Default")
      (node (ref "U$2") (pin "P$3") (pinfunction "C_P$3") (pintype "input"))
      (node (ref "U1") (pin "26") (pinfunction "SA_26") (pintype "output"))
      (node (ref "U1") (pin "9") (pinfunction "SA_2_9") (pintype "output"))
    )
    (net (code "46") (name "/R_YB") (class "Default")
      (node (ref "U$2") (pin "P$2") (pinfunction "B_P$2") (pintype "input"))
      (node (ref "U1") (pin "11") (pinfunction "SB_2_11") (pintype "output"))
      (node (ref "U1") (pin "24") (pinfunction "SB_24") (pintype "output"))
    )
    (net (code "47") (name "/R_YC") (class "Default")
      (node (ref "U$2") (pin "P$1") (pinfunction "A_P$1") (pintype "input"))
      (node (ref "U1") (pin "13") (pinfunction "SC_2_13") (pintype "output"))
      (node (ref "U1") (pin "22") (pinfunction "SC_22") (pintype "output"))
    )
    (net (code "48") (name "/SCL") (class "Default")
      (node (ref "R14") (pin "1") (pinfunction "1_1") (pintype "passive"))
      (node (ref "U$3") (pin "P$13") (pinfunction "SCL_P$13") (pintype "bidirectional"))
      (node (ref "U2") (pin "83") (pinfunction "PD2_83") (pintype "bidirectional"))
    )
    (net (code "49") (name "/SDA") (class "Default")
      (node (ref "R13") (pin "1") (pinfunction "1_1") (pintype "passive"))
      (node (ref "U$3") (pin "P$14") (pinfunction "SDA_P$14") (pintype "bidirectional"))
      (node (ref "U2") (pin "82") (pinfunction "PD1_82") (pintype "bidirectional"))
    )
    (net (code "50") (name "/SWCLK") (class "Default")
      (node (ref "J1") (pin "4") (pinfunction "4_4") (pintype "passive"))
      (node (ref "U2") (pin "76") (pinfunction "PA14_76") (pintype "bidirectional"))
    )
    (net (code "51") (name "/SWDIO") (class "Default")
      (node (ref "J1") (pin "6") (pinfunction "6_6") (pintype "passive"))
      (node (ref "U2") (pin "72") (pinfunction "PA13_72") (pintype "bidirectional"))
    )
    (net (code "52") (name "/UART_RX") (class "Default")
      (node (ref "J1") (pin "3") (pinfunction "3_3") (pintype "passive"))
      (node (ref "U2") (pin "69") (pinfunction "PA10_69") (pintype "bidirectional"))
    )
    (net (code "53") (name "/UART_TX") (class "Default")
      (node (ref "J1") (pin "5") (pinfunction "5_5") (pintype "passive"))
      (node (ref "U2") (pin "68") (pinfunction "PA9_68") (pintype "bidirectional"))
    )
    (net (code "54") (name "/VBAT") (class "Default")
      (node (ref "U2") (pin "6") (pinfunction "VBAT_6") (pintype "power_in"))
    )
    (net (code "55") (name "GND") (class "Default")
      (node (ref "C1") (pin "2") (pinfunction "2_2") (pintype "passive"))
      (node (ref "C13") (pin "2") (pinfunction "2_2") (pintype "passive"))
      (node (ref "C15") (pin "2") (pinfunction "2_2") (pintype "passive"))
      (node (ref "C16") (pin "2") (pinfunction "2_2") (pintype "passive"))
      (node (ref "C17") (pin "1") (pinfunction "1_1") (pintype "passive"))
      (node (ref "C18") (pin "1") (pinfunction "1_1") (pintype "passive"))
      (node (ref "C19") (pin "2") (pinfunction "2_2") (pintype "passive"))
      (node (ref "C20") (pin "2") (pinfunction "2_2") (pintype "passive"))
      (node (ref "C21") (pin "2") (pinfunction "2_2") (pintype "passive"))
      (node (ref "C22") (pin "2") (pinfunction "2_2") (pintype "passive"))
      (node (ref "C23") (pin "1") (pinfunction "1_1") (pintype "passive"))
      (node (ref "C24") (pin "2") (pinfunction "2_2") (pintype "passive"))
      (node (ref "C25") (pin "1") (pinfunction "1_1") (pintype "passive"))
      (node (ref "C26") (pin "1") (pinfunction "1_1") (pintype "passive"))
      (node (ref "C27") (pin "2") (pinfunction "2_2") (pintype "passive"))
      (node (ref "C28") (pin "2") (pinfunction "2_2") (pintype "passive"))
      (node (ref "C29") (pin "2") (pinfunction "2_2") (pintype "passive"))
      (node (ref "C32") (pin "1") (pinfunction "1_1") (pintype "passive"))
      (node (ref "C33") (pin "1") (pinfunction "1_1") (pintype "passive"))
      (node (ref "C34") (pin "-") (pinfunction "-_-") (pintype "passive"))
      (node (ref "C35") (pin "2") (pinfunction "2_2") (pintype "passive"))
      (node (ref "C36") (pin "2") (pinfunction "2_2") (pintype "passive"))
      (node (ref "C37") (pin "2") (pinfunction "2_2") (pintype "passive"))
      (node (ref "C38") (pin "2") (pinfunction "2_2") (pintype "passive"))
      (node (ref "C4") (pin "-") (pinfunction "-_-") (pintype "passive"))
      (node (ref "C40") (pin "1") (pinfunction "1_1") (pintype "passive"))
      (node (ref "C41") (pin "1") (pinfunction "1_1") (pintype "passive"))
      (node (ref "C42") (pin "1") (pinfunction "1_1") (pintype "passive"))
      (node (ref "C43") (pin "1") (pinfunction "1_1") (pintype "passive"))
      (node (ref "C44") (pin "1") (pinfunction "1_1") (pintype "passive"))
      (node (ref "C5") (pin "2") (pinfunction "2_2") (pintype "passive"))
      (node (ref "C6") (pin "2") (pinfunction "2_2") (pintype "passive"))
      (node (ref "C7") (pin "2") (pinfunction "2_2") (pintype "passive"))
      (node (ref "C8") (pin "2") (pinfunction "2_2") (pintype "passive"))
      (node (ref "C9") (pin "2") (pinfunction "2_2") (pintype "passive"))
      (node (ref "IR_FRONT_S1") (pin "A") (pinfunction "A_A") (pintype "passive"))
      (node (ref "IR_FRONT_S2") (pin "A") (pinfunction "A_A") (pintype "passive"))
      (node (ref "IR_LEFT_S") (pin "A") (pinfunction "A_A") (pintype "passive"))
      (node (ref "IR_RIGHT_S") (pin "A") (pinfunction "A_A") (pintype "passive"))
      (node (ref "J1") (pin "7") (pinfunction "7_7") (pintype "passive"))
      (node (ref "J1") (pin "8") (pinfunction "8_8") (pintype "passive"))
      (node (ref "JP1") (pin "1") (pinfunction "1_1") (pintype "passive"))
      (node (ref "LED10") (pin "C") (pinfunction "C_C") (pintype "passive"))
      (node (ref "LED11") (pin "C") (pinfunction "C_C") (pintype "passive"))
      (node (ref "LED12") (pin "C") (pinfunction "C_C") (pintype "passive"))
      (node (ref "LED9") (pin "C") (pinfunction "C_C") (pintype "passive"))
      (node (ref "L_ENCODER") (pin "1") (pinfunction "1_1") (pintype "passive"))
      (node (ref "L_ENCODER1") (pin "1") (pinfunction "1_1") (pintype "passive"))
      (node (ref "Q10") (pin "E") (pinfunction "E_E") (pintype "passive"))
      (node (ref "Q11") (pin "E") (pinfunction "E_E") (pintype "passive"))
      (node (ref "Q2") (pin "2") (pinfunction "S_2") (pintype "passive"))
      (node (ref "Q3") (pin "2") (pinfunction "S_2") (pintype "passive"))
      (node (ref "Q4") (pin "E") (pinfunction "E_E") (pintype "passive"))
      (node (ref "Q5") (pin "E") (pinfunction "E_E") (pintype "passive"))
      (node (ref "Q6") (pin "E") (pinfunction "E_E") (pintype "passive"))
      (node (ref "Q7") (pin "E") (pinfunction "E_E") (pintype "passive"))
      (node (ref "Q8") (pin "E") (pinfunction "E_E") (pintype "passive"))
      (node (ref "Q9") (pin "E") (pinfunction "E_E") (pintype "passive"))
      (node (ref "R1") (pin "1") (pinfunction "1_1") (pintype "passive"))
      (node (ref "R3") (pin "1") (pinfunction "1_1") (pintype "passive"))
      (node (ref "R30") (pin "1") (pinfunction "1_1") (pintype "passive"))
      (node (ref "R36") (pin "1") (pinfunction "1_1") (pintype "passive"))
      (node (ref "R39") (pin "1") (pinfunction "1_1") (pintype "passive"))
      (node (ref "RESET") (pin "1") (pinfunction "1_1") (pintype "passive"))
      (node (ref "RESET") (pin "2") (pinfunction "2_2") (pintype "passive"))
      (node (ref "U$3") (pin "P$1") (pinfunction "SDO/SA0_P$1") (pintype "bidirectional"))
      (node (ref "U$3") (pin "P$2") (pinfunction "SDX_P$2") (pintype "bidirectional"))
      (node (ref "U$3") (pin "P$3") (pinfunction "SCX_P$3") (pintype "bidirectional"))
      (node (ref "U$3") (pin "P$6") (pinfunction "GND1_P$6") (pintype "bidirectional"))
      (node (ref "U$3") (pin "P$7") (pinfunction "GND2_P$7") (pintype "bidirectional"))
      (node (ref "U$4") (pin "P$2") (pinfunction "GND_P$2") (pintype "bidirectional"))
      (node (ref "U$4") (pin "P$5") (pinfunction "WP_P$5") (pintype "bidirectional"))
      (node (ref "U1") (pin "18") (pinfunction "GND_18") (pintype "passive"))
      (node (ref "U2") (pin "10") (pinfunction "VSS_2_10") (pintype "passive"))
      (node (ref "U2") (pin "19") (pinfunction "VSSA_19") (pintype "passive"))
      (node (ref "U2") (pin "26") (pinfunction "VSS_26") (pintype "passive"))
      (node (ref "U2") (pin "49") (pinfunction "VSS_4_49") (pintype "power_in"))
      (node (ref "U2") (pin "74") (pinfunction "VSS_2_74") (pintype "passive"))
      (node (ref "U2") (pin "99") (pinfunction "VSS_99") (pintype "passive"))
      (node (ref "U3") (pin "18") (pinfunction "GND_18") (pintype "passive"))
      (node (ref "U4") (pin "4") (pinfunction "GND_4") (pintype "bidirectional"))
      (node (ref "USER") (pin "1") (pinfunction "1_1") (pintype "passive"))
      (node (ref "USER") (pin "2") (pinfunction "2_2") (pintype "passive"))
    )
    (net (code "56") (name "Net-(IR_LEFT-PadA)") (class "Default")
      (node (ref "IR_LEFT") (pin "A") (pinfunction "A_A") (pintype "passive"))
      (node (ref "R33") (pin "1") (pinfunction "1_1") (pintype "passive"))
    )
    (net (code "57") (name "Net-(IR_RIGHT-PadA)") (class "Default")
      (node (ref "IR_RIGHT") (pin "A") (pinfunction "A_A") (pintype "passive"))
      (node (ref "R31") (pin "1") (pinfunction "1_1") (pintype "passive"))
    )
    (net (code "58") (name "Net-(IR_RIGHT1-PadA)") (class "Default")
      (node (ref "IR_RIGHT1") (pin "A") (pinfunction "A_A") (pintype "passive"))
      (node (ref "R29") (pin "1") (pinfunction "1_1") (pintype "passive"))
    )
    (net (code "59") (name "Net-(L1-1)") (class "Default")
      (node (ref "C39") (pin "1") (pinfunction "1_1") (pintype "passive"))
      (node (ref "L1") (pin "P$1") (pinfunction "1_P$1") (pintype "passive"))
      (node (ref "U4") (pin "5") (pinfunction "SW_5") (pintype "bidirectional"))
    )
    (net (code "60") (name "Net-(LED1-PadA)") (class "Default")
      (node (ref "LED1") (pin "A") (pinfunction "A_A") (pintype "passive"))
      (node (ref "R5") (pin "1") (pinfunction "1_1") (pintype "passive"))
    )
    (net (code "61") (name "Net-(LED2-PadA)") (class "Default")
      (node (ref "LED2") (pin "A") (pinfunction "A_A") (pintype "passive"))
      (node (ref "R10") (pin "1") (pinfunction "1_1") (pintype "passive"))
    )
    (net (code "62") (name "Net-(LED3-PadA)") (class "Default")
      (node (ref "LED3") (pin "A") (pinfunction "A_A") (pintype "passive"))
      (node (ref "R12") (pin "1") (pinfunction "1_1") (pintype "passive"))
    )
    (net (code "63") (name "Net-(LED4-PadA)") (class "Default")
      (node (ref "LED4") (pin "A") (pinfunction "A_A") (pintype "passive"))
      (node (ref "R17") (pin "1") (pinfunction "1_1") (pintype "passive"))
    )
    (net (code "64") (name "Net-(LED5-PadA)") (class "Default")
      (node (ref "LED5") (pin "A") (pinfunction "A_A") (pintype "passive"))
      (node (ref "R19") (pin "1") (pinfunction "1_1") (pintype "passive"))
    )
    (net (code "65") (name "Net-(LED6-PadA)") (class "Default")
      (node (ref "LED6") (pin "A") (pinfunction "A_A") (pintype "passive"))
      (node (ref "R21") (pin "1") (pinfunction "1_1") (pintype "passive"))
    )
    (net (code "66") (name "Net-(LED7-PadA)") (class "Default")
      (node (ref "LED7") (pin "A") (pinfunction "A_A") (pintype "passive"))
      (node (ref "R23") (pin "1") (pinfunction "1_1") (pintype "passive"))
    )
    (net (code "67") (name "Net-(LED8-PadA)") (class "Default")
      (node (ref "LED8") (pin "A") (pinfunction "A_A") (pintype "passive"))
      (node (ref "R25") (pin "1") (pinfunction "1_1") (pintype "passive"))
    )
    (net (code "68") (name "Net-(LED9-PadA)") (class "Default")
      (node (ref "LED9") (pin "A") (pinfunction "A_A") (pintype "passive"))
      (node (ref "R9") (pin "1") (pinfunction "1_1") (pintype "passive"))
    )
    (net (code "69") (name "Net-(LED10-PadA)") (class "Default")
      (node (ref "LED10") (pin "A") (pinfunction "A_A") (pintype "passive"))
      (node (ref "R38") (pin "1") (pinfunction "1_1") (pintype "passive"))
    )
    (net (code "70") (name "Net-(LED11-PadA)") (class "Default")
      (node (ref "LED11") (pin "A") (pinfunction "A_A") (pintype "passive"))
      (node (ref "R28") (pin "1") (pinfunction "1_1") (pintype "passive"))
    )
    (net (code "71") (name "Net-(LED12-PadA)") (class "Default")
      (node (ref "LED12") (pin "A") (pinfunction "A_A") (pintype "passive"))
      (node (ref "R27") (pin "2") (pinfunction "2_2") (pintype "passive"))
    )
    (net (code "72") (name "Net-(U1-CP1)") (class "Default")
      (node (ref "C2") (pin "2") (pinfunction "2_2") (pintype "passive"))
      (node (ref "U1") (pin "20") (pinfunction "CP1_20") (pintype "passive"))
    )
    (net (code "73") (name "Net-(U1-CP2)") (class "Default")
      (node (ref "C2") (pin "1") (pinfunction "1_1") (pintype "passive"))
      (node (ref "U1") (pin "21") (pinfunction "CP2_21") (pintype "passive"))
    )
    (net (code "74") (name "Net-(U1-LSS)") (class "Default")
      (node (ref "R1") (pin "2") (pinfunction "2_2") (pintype "passive"))
      (node (ref "R8") (pin "1") (pinfunction "1_1") (pintype "passive"))
      (node (ref "U1") (pin "10") (pinfunction "LSS_2_10") (pintype "passive"))
      (node (ref "U1") (pin "12") (pinfunction "LSS_12") (pintype "passive"))
    )
    (net (code "75") (name "Net-(U1-VCP)") (class "Default")
      (node (ref "C3") (pin "1") (pinfunction "1_1") (pintype "passive"))
      (node (ref "U1") (pin "19") (pinfunction "VCP_19") (pintype "output"))
    )
    (net (code "76") (name "Net-(U1-VG)") (class "Default")
      (node (ref "C1") (pin "1") (pinfunction "1_1") (pintype "passive"))
      (node (ref "U1") (pin "14") (pinfunction "VG_14") (pintype "power_in"))
    )
    (net (code "77") (name "Net-(U2A-VCAP_1)") (class "Default")
      (node (ref "C23") (pin "2") (pinfunction "2_2") (pintype "passive"))
      (node (ref "U2") (pin "48") (pinfunction "VCAP_1_48") (pintype "power_in"))
    )
    (net (code "78") (name "Net-(U2B-VCAP_2)") (class "Default")
      (node (ref "C19") (pin "1") (pinfunction "1_1") (pintype "passive"))
      (node (ref "U2") (pin "73") (pinfunction "VCAP_2_73") (pintype "power_in"))
    )
    (net (code "79") (name "Net-(U3-CP1)") (class "Default")
      (node (ref "C30") (pin "2") (pinfunction "2_2") (pintype "passive"))
      (node (ref "U3") (pin "20") (pinfunction "CP1_20") (pintype "passive"))
    )
    (net (code "80") (name "Net-(U3-CP2)") (class "Default")
      (node (ref "C30") (pin "1") (pinfunction "1_1") (pintype "passive"))
      (node (ref "U3") (pin "21") (pinfunction "CP2_21") (pintype "passive"))
    )
    (net (code "81") (name "Net-(U3-LSS)") (class "Default")
      (node (ref "R36") (pin "2") (pinfunction "2_2") (pintype "passive"))
      (node (ref "R7") (pin "1") (pinfunction "1_1") (pintype "passive"))
      (node (ref "U3") (pin "10") (pinfunction "LSS_2_10") (pintype "passive"))
      (node (ref "U3") (pin "12") (pinfunction "LSS_12") (pintype "passive"))
    )
    (net (code "82") (name "Net-(U3-VCP)") (class "Default")
      (node (ref "C31") (pin "1") (pinfunction "1_1") (pintype "passive"))
      (node (ref "U3") (pin "19") (pinfunction "VCP_19") (pintype "output"))
    )
    (net (code "83") (name "Net-(U3-VG)") (class "Default")
      (node (ref "C13") (pin "1") (pinfunction "1_1") (pintype "passive"))
      (node (ref "U3") (pin "14") (pinfunction "VG_14") (pintype "power_in"))
    )
    (net (code "84") (name "Net-(U4-BST)") (class "Default")
      (node (ref "C39") (pin "2") (pinfunction "2_2") (pintype "passive"))
      (node (ref "U4") (pin "6") (pinfunction "BST_6") (pintype "bidirectional"))
    )
    (net (code "85") (name "VCC") (class "Default")
      (node (ref "C17") (pin "2") (pinfunction "2_2") (pintype "passive"))
      (node (ref "C18") (pin "2") (pinfunction "2_2") (pintype "passive"))
      (node (ref "C3") (pin "2") (pinfunction "2_2") (pintype "passive"))
      (node (ref "C31") (pin "2") (pinfunction "2_2") (pintype "passive"))
      (node (ref "C32") (pin "2") (pinfunction "2_2") (pintype "passive"))
      (node (ref "C33") (pin "2") (pinfunction "2_2") (pintype "passive"))
      (node (ref "C34") (pin "+") (pinfunction "+_+") (pintype "passive"))
      (node (ref "C4") (pin "+") (pinfunction "+_+") (pintype "passive"))
      (node (ref "C40") (pin "2") (pinfunction "2_2") (pintype "passive"))
      (node (ref "C41") (pin "2") (pinfunction "2_2") (pintype "passive"))
      (node (ref "JP1") (pin "2") (pinfunction "2_2") (pintype "passive"))
      (node (ref "U1") (pin "23") (pinfunction "VIN_2_23") (pintype "power_in"))
      (node (ref "U1") (pin "25") (pinfunction "VIN_25") (pintype "power_in"))
      (node (ref "U3") (pin "23") (pinfunction "VIN_2_23") (pintype "power_in"))
      (node (ref "U3") (pin "25") (pinfunction "VIN_25") (pintype "power_in"))
      (node (ref "U4") (pin "2") (pinfunction "EN_2") (pintype "bidirectional"))
      (node (ref "U4") (pin "3") (pinfunction "VIN_3") (pintype "bidirectional"))
    )
    (net (code "86") (name "unconnected-(U$3-INT1-PadP$4)") (class "Default")
      (node (ref "U$3") (pin "P$4") (pinfunction "INT1_P$4") (pintype "bidirectional"))
    )
    (net (code "87") (name "unconnected-(U$3-INT2-PadP$9)") (class "Default")
      (node (ref "U$3") (pin "P$9") (pinfunction "INT2_P$9") (pintype "bidirectional"))
    )
    (net (code "88") (name "unconnected-(U$3-NC1-PadP$10)") (class "Default")
      (node (ref "U$3") (pin "P$10") (pinfunction "NC1_P$10") (pintype "bidirectional"))
    )
    (net (code "89") (name "unconnected-(U$3-NC2-PadP$11)") (class "Default")
      (node (ref "U$3") (pin "P$11") (pinfunction "NC2_P$11") (pintype "bidirectional"))
    )
    (net (code "90") (name "unconnected-(U1-NFAULT-Pad1)") (class "Default")
      (node (ref "U1") (pin "1") (pinfunction "NFAULT_1") (pintype "output"))
    )
    (net (code "91") (name "unconnected-(U1-SOA-Pad15)") (class "Default")
      (node (ref "U1") (pin "15") (pinfunction "SOA_15") (pintype "output"))
    )
    (net (code "92") (name "unconnected-(U1-SOB-Pad16)") (class "Default")
      (node (ref "U1") (pin "16") (pinfunction "SOB_16") (pintype "output"))
    )
    (net (code "93") (name "unconnected-(U1-SOC-Pad17)") (class "Default")
      (node (ref "U1") (pin "17") (pinfunction "SOC_17") (pintype "output"))
    )
    (net (code "94") (name "unconnected-(U2A-PB2-Pad36)") (class "Default")
      (node (ref "U2") (pin "36") (pinfunction "PB2_36") (pintype "bidirectional"))
    )
    (net (code "95") (name "unconnected-(U2A-PB10-Pad46)") (class "Default")
      (node (ref "U2") (pin "46") (pinfunction "PB10_46") (pintype "bidirectional"))
    )
    (net (code "96") (name "unconnected-(U2A-PB11-Pad47)") (class "Default")
      (node (ref "U2") (pin "47") (pinfunction "PB11_47") (pintype "bidirectional"))
    )
    (net (code "97") (name "unconnected-(U2A-PC0-Pad15)") (class "Default")
      (node (ref "U2") (pin "15") (pinfunction "PC0_15") (pintype "bidirectional"))
    )
    (net (code "98") (name "unconnected-(U2A-PC1-Pad16)") (class "Default")
      (node (ref "U2") (pin "16") (pinfunction "PC1_16") (pintype "bidirectional"))
    )
    (net (code "99") (name "unconnected-(U2A-PC13-Pad7)") (class "Default")
      (node (ref "U2") (pin "7") (pinfunction "PC13_7") (pintype "bidirectional"))
    )
    (net (code "100") (name "unconnected-(U2A-PE5-Pad4)") (class "Default")
      (node (ref "U2") (pin "4") (pinfunction "PE5_4") (pintype "bidirectional"))
    )
    (net (code "101") (name "unconnected-(U2A-PE6-Pad5)") (class "Default")
      (node (ref "U2") (pin "5") (pinfunction "PE6_5") (pintype "bidirectional"))
    )
    (net (code "102") (name "unconnected-(U2A-PE7-Pad37)") (class "Default")
      (node (ref "U2") (pin "37") (pinfunction "PE7_37") (pintype "bidirectional"))
    )
    (net (code "103") (name "unconnected-(U2A-PE8-Pad38)") (class "Default")
      (node (ref "U2") (pin "38") (pinfunction "PE8_38") (pintype "bidirectional"))
    )
    (net (code "104") (name "unconnected-(U2A-PE9-Pad39)") (class "Default")
      (node (ref "U2") (pin "39") (pinfunction "PE9_39") (pintype "bidirectional"))
    )
    (net (code "105") (name "unconnected-(U2A-PE10-Pad40)") (class "Default")
      (node (ref "U2") (pin "40") (pinfunction "PE10_40") (pintype "bidirectional"))
    )
    (net (code "106") (name "unconnected-(U2A-PE11-Pad41)") (class "Default")
      (node (ref "U2") (pin "41") (pinfunction "PE11_41") (pintype "bidirectional"))
    )
    (net (code "107") (name "unconnected-(U2A-PE12-Pad42)") (class "Default")
      (node (ref "U2") (pin "42") (pinfunction "PE12_42") (pintype "bidirectional"))
    )
    (net (code "108") (name "unconnected-(U2A-PE13-Pad43)") (class "Default")
      (node (ref "U2") (pin "43") (pinfunction "PE13_43") (pintype "bidirectional"))
    )
    (net (code "109") (name "unconnected-(U2A-PE14-Pad44)") (class "Default")
      (node (ref "U2") (pin "44") (pinfunction "PE14_44") (pintype "bidirectional"))
    )
    (net (code "110") (name "unconnected-(U2A-PE15-Pad45)") (class "Default")
      (node (ref "U2") (pin "45") (pinfunction "PE15_45") (pintype "bidirectional"))
    )
    (net (code "111") (name "unconnected-(U2B-PA12-Pad71)") (class "Default")
      (node (ref "U2") (pin "71") (pinfunction "PA12_71") (pintype "bidirectional"))
    )
    (net (code "112") (name "unconnected-(U2B-PA15-Pad77)") (class "Default")
      (node (ref "U2") (pin "77") (pinfunction "PA15_77") (pintype "bidirectional"))
    )
    (net (code "113") (name "unconnected-(U2B-PA_11-Pad70)") (class "Default")
      (node (ref "U2") (pin "70") (pinfunction "PA_11_70") (pintype "bidirectional"))
    )
    (net (code "114") (name "unconnected-(U2B-PB3-Pad89)") (class "Default")
      (node (ref "U2") (pin "89") (pinfunction "PB3_89") (pintype "bidirectional"))
    )
    (net (code "115") (name "unconnected-(U2B-PB4-Pad90)") (class "Default")
      (node (ref "U2") (pin "90") (pinfunction "PB4_90") (pintype "bidirectional"))
    )
    (net (code "116") (name "unconnected-(U2B-PB5-Pad91)") (class "Default")
      (node (ref "U2") (pin "91") (pinfunction "PB5_91") (pintype "bidirectional"))
    )
    (net (code "117") (name "unconnected-(U2B-PB12-Pad51)") (class "Default")
      (node (ref "U2") (pin "51") (pinfunction "PB12_51") (pintype "bidirectional"))
    )
    (net (code "118") (name "unconnected-(U2B-PB13-Pad52)") (class "Default")
      (node (ref "U2") (pin "52") (pinfunction "PB13_52") (pintype "bidirectional"))
    )
    (net (code "119") (name "unconnected-(U2B-PB14-Pad53)") (class "Default")
      (node (ref "U2") (pin "53") (pinfunction "PB14_53") (pintype "bidirectional"))
    )
    (net (code "120") (name "unconnected-(U2B-PB15-Pad54)") (class "Default")
      (node (ref "U2") (pin "54") (pinfunction "PB15_54") (pintype "bidirectional"))
    )
    (net (code "121") (name "unconnected-(U2B-PC6-Pad63)") (class "Default")
      (node (ref "U2") (pin "63") (pinfunction "PC6_63") (pintype "bidirectional"))
    )
    (net (code "122") (name "unconnected-(U2B-PC10-Pad78)") (class "Default")
      (node (ref "U2") (pin "78") (pinfunction "PC10_78") (pintype "bidirectional"))
    )
    (net (code "123") (name "unconnected-(U2B-PC11-Pad79)") (class "Default")
      (node (ref "U2") (pin "79") (pinfunction "PC11_79") (pintype "bidirectional"))
    )
    (net (code "124") (name "unconnected-(U2B-PC12-Pad80)") (class "Default")
      (node (ref "U2") (pin "80") (pinfunction "PC12_80") (pintype "bidirectional"))
    )
    (net (code "125") (name "unconnected-(U2B-PD0-Pad81)") (class "Default")
      (node (ref "U2") (pin "81") (pinfunction "PD0_81") (pintype "bidirectional"))
    )
    (net (code "126") (name "unconnected-(U2B-PD5-Pad86)") (class "Default")
      (node (ref "U2") (pin "86") (pinfunction "PD5_86") (pintype "bidirectional"))
    )
    (net (code "127") (name "unconnected-(U2B-PD6-Pad87)") (class "Default")
      (node (ref "U2") (pin "87") (pinfunction "PD6_87") (pintype "bidirectional"))
    )
    (net (code "128") (name "unconnected-(U2B-PD7-Pad88)") (class "Default")
      (node (ref "U2") (pin "88") (pinfunction "PD7_88") (pintype "bidirectional"))
    )
    (net (code "129") (name "unconnected-(U2B-PD8-Pad55)") (class "Default")
      (node (ref "U2") (pin "55") (pinfunction "PD8_55") (pintype "bidirectional"))
    )
    (net (code "130") (name "unconnected-(U2B-PD9-Pad56)") (class "Default")
      (node (ref "U2") (pin "56") (pinfunction "PD9_56") (pintype "bidirectional"))
    )
    (net (code "131") (name "unconnected-(U2B-PD10-Pad57)") (class "Default")
      (node (ref "U2") (pin "57") (pinfunction "PD10_57") (pintype "bidirectional"))
    )
    (net (code "132") (name "unconnected-(U2B-PD11-Pad58)") (class "Default")
      (node (ref "U2") (pin "58") (pinfunction "PD11_58") (pintype "bidirectional"))
    )
    (net (code "133") (name "unconnected-(U2B-PD12-Pad59)") (class "Default")
      (node (ref "U2") (pin "59") (pinfunction "PD12_59") (pintype "bidirectional"))
    )
    (net (code "134") (name "unconnected-(U3-NFAULT-Pad1)") (class "Default")
      (node (ref "U3") (pin "1") (pinfunction "NFAULT_1") (pintype "output"))
    )
    (net (code "135") (name "unconnected-(U3-SOA-Pad15)") (class "Default")
      (node (ref "U3") (pin "15") (pinfunction "SOA_15") (pintype "output"))
    )
    (net (code "136") (name "unconnected-(U3-SOB-Pad16)") (class "Default")
      (node (ref "U3") (pin "16") (pinfunction "SOB_16") (pintype "output"))
    )
    (net (code "137") (name "unconnected-(U3-SOC-Pad17)") (class "Default")
      (node (ref "U3") (pin "17") (pinfunction "SOC_17") (pintype "output"))
    )
    (net (code "138") (name "unconnected-(USER-Pad3)") (class "Default")
      (node (ref "USER") (pin "3") (pinfunction "3_3") (pintype "passive"))
    )
  )
)
